# E565AFEE.net
KiCad netlist of a schematic drawn in EAGLE
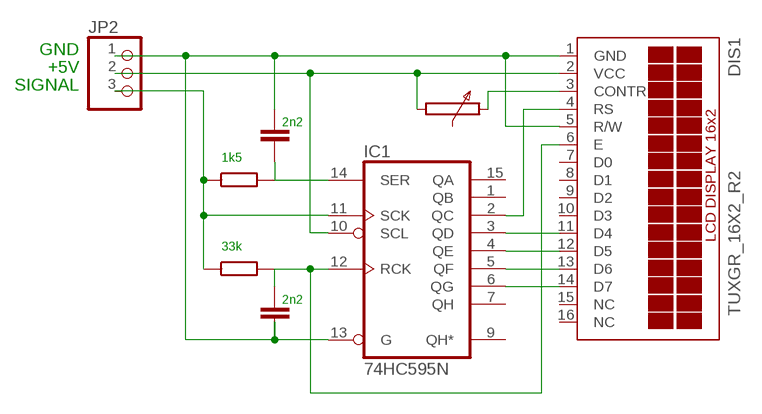
[diagram p0: schematic, sheet 1]

(export (version "E")
  (design (tool "Eeschema 10.0.6"))
  (components
    (comp (ref "DIS1")
      (value "TUXGR_16X2_R2")
      (footprint "eagle-import:TUXGR_16X2_R2")
      (libsource (lib "eagle-import") (part "TUXGR_16X2_R2"))
    )
    (comp (ref "IC1")
      (value "74HC595N")
      (footprint "eagle-import:DIL16")
      (libsource (lib "eagle-import") (part "74595NHC"))
    )
    (comp (ref "JP2")
      (value "PINHD-1X3")
      (footprint "eagle-import:1X03")
      (libsource (lib "eagle-import") (part "PINHD-1X3"))
    )
  )
  (nets
    (net (code "1") (name "Net-(DIS1-D4)") (class "Default")
      (node (ref "DIS1") (pin "11") (pinfunction "D4_11") (pintype "input"))
      (node (ref "IC1") (pin "3") (pinfunction "QD_3") (pintype "tri_state"))
    )
    (net (code "2") (name "Net-(DIS1-D5)") (class "Default")
      (node (ref "DIS1") (pin "12") (pinfunction "D5_12") (pintype "input"))
      (node (ref "IC1") (pin "4") (pinfunction "QE_4") (pintype "tri_state"))
    )
    (net (code "3") (name "Net-(DIS1-D6)") (class "Default")
      (node (ref "DIS1") (pin "13") (pinfunction "D6_13") (pintype "input"))
      (node (ref "IC1") (pin "5") (pinfunction "QF_5") (pintype "tri_state"))
    )
    (net (code "4") (name "Net-(DIS1-D7)") (class "Default")
      (node (ref "DIS1") (pin "14") (pinfunction "D7_14") (pintype "input"))
      (node (ref "IC1") (pin "6") (pinfunction "QG_6") (pintype "tri_state"))
    )
    (net (code "5") (name "Net-(DIS1-E)") (class "Default")
      (node (ref "DIS1") (pin "6") (pinfunction "E_6") (pintype "input"))
      (node (ref "IC1") (pin "12") (pinfunction "RCK_12") (pintype "input"))
    )
    (net (code "6") (name "Net-(DIS1-GND)") (class "Default")
      (node (ref "DIS1") (pin "1") (pinfunction "GND_1") (pintype "power_in"))
      (node (ref "DIS1") (pin "5") (pinfunction "R/W_5") (pintype "input"))
      (node (ref "IC1") (pin "13") (pinfunction "G_13") (pintype "input"))
      (node (ref "JP2") (pin "1") (pinfunction "1_1") (pintype "passive"))
    )
    (net (code "7") (name "Net-(DIS1-RS)") (class "Default")
      (node (ref "DIS1") (pin "4") (pinfunction "RS_4") (pintype "input"))
      (node (ref "IC1") (pin "2") (pinfunction "QC_2") (pintype "tri_state"))
    )
    (net (code "8") (name "Net-(DIS1-VCC)") (class "Default")
      (node (ref "DIS1") (pin "2") (pinfunction "VCC_2") (pintype "power_in"))
      (node (ref "IC1") (pin "10") (pinfunction "SCL_10") (pintype "input"))
      (node (ref "JP2") (pin "2") (pinfunction "2_2") (pintype "passive"))
    )
    (net (code "9") (name "Net-(IC1A-SCK)") (class "Default")
      (node (ref "IC1") (pin "11") (pinfunction "SCK_11") (pintype "input"))
      (node (ref "JP2") (pin "3") (pinfunction "3_3") (pintype "passive"))
    )
    (net (code "10") (name "unconnected-(DIS1-CONTR-Pad3)") (class "Default")
      (node (ref "DIS1") (pin "3") (pinfunction "CONTR_3") (pintype "input"))
    )
    (net (code "11") (name "unconnected-(DIS1-D0-Pad7)") (class "Default")
      (node (ref "DIS1") (pin "7") (pinfunction "D0_7") (pintype "input"))
    )
    (net (code "12") (name "unconnected-(DIS1-D1-Pad8)") (class "Default")
      (node (ref "DIS1") (pin "8") (pinfunction "D1_8") (pintype "input"))
    )
    (net (code "13") (name "unconnected-(DIS1-D2-Pad9)") (class "Default")
      (node (ref "DIS1") (pin "9") (pinfunction "D2_9") (pintype "input"))
    )
    (net (code "14") (name "unconnected-(DIS1-D3-Pad10)") (class "Default")
      (node (ref "DIS1") (pin "10") (pinfunction "D3_10") (pintype "input"))
    )
    (net (code "15") (name "unconnected-(DIS1-NC-Pad15)") (class "Default")
      (node (ref "DIS1") (pin "15") (pinfunction "NC_15") (pintype "no_connect"))
    )
    (net (code "16") (name "unconnected-(DIS1-NC-Pad16)") (class "Default")
      (node (ref "DIS1") (pin "16") (pinfunction "NC_16") (pintype "no_connect"))
    )
    (net (code "17") (name "unconnected-(IC1A-QA-Pad15)") (class "Default")
      (node (ref "IC1") (pin "15") (pinfunction "QA_15") (pintype "tri_state"))
    )
    (net (code "18") (name "unconnected-(IC1A-QB-Pad1)") (class "Default")
      (node (ref "IC1") (pin "1") (pinfunction "QB_1") (pintype "tri_state"))
    )
    (net (code "19") (name "unconnected-(IC1A-QH*-Pad9)") (class "Default")
      (node (ref "IC1") (pin "9") (pinfunction "QH*_9") (pintype "tri_state"))
    )
    (net (code "20") (name "unconnected-(IC1A-QH-Pad7)") (class "Default")
      (node (ref "IC1") (pin "7") (pinfunction "QH_7") (pintype "tri_state"))
    )
    (net (code "21") (name "unconnected-(IC1A-SER-Pad14)") (class "Default")
      (node (ref "IC1") (pin "14") (pinfunction "SER_14") (pintype "input"))
    )
  )
)
